# arm_schematic.net
KiCad netlist of a schematic drawn in EAGLE
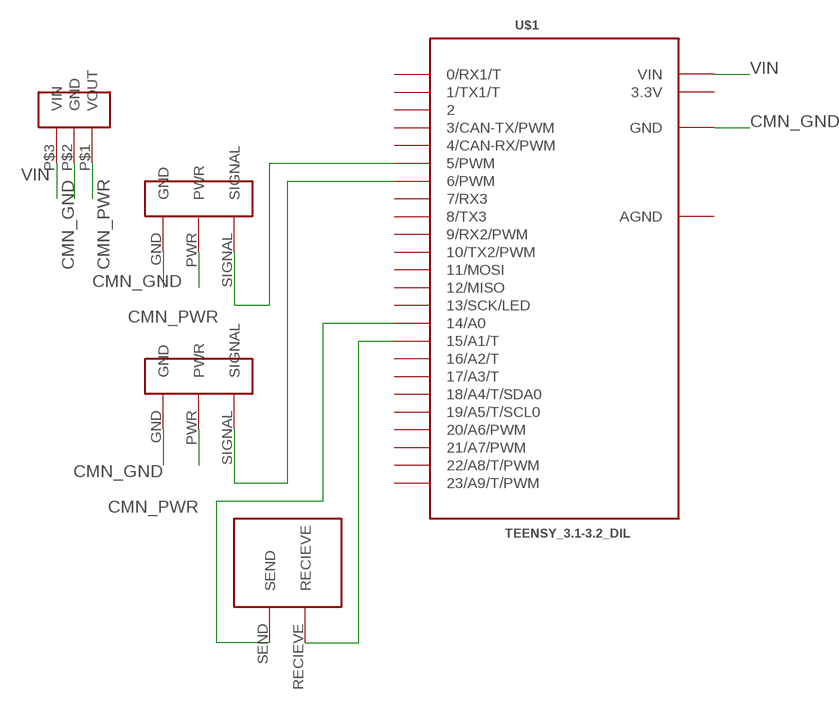
[diagram p0: schematic, sheet 1]

(export (version "E")
  (design (tool "Eeschema 10.0.6"))
  (components
    (comp (ref "U$1")
      (value "TEENSY_3.1-3.2_DIL")
      (footprint "eagle-import:TEENSY_3.0-3.2&LC_DIL")
      (libsource (lib "eagle-import") (part "TEENSY_3.1-3.2_DIL"))
    )
    (comp (ref "U$2")
      (value "VOLTAGE_REGULATOR")
      (footprint "eagle-import:VOLTAGE_REGULATOR")
      (libsource (lib "eagle-import") (part "VOLTAGE_REGULATOR"))
    )
    (comp (ref "U$3")
      (value "CUSTOM_BIT_COMM")
      (footprint "eagle-import:CUSTOM_BIT_COMM")
      (libsource (lib "eagle-import") (part "CUSTOM_BIT_COMM"))
    )
    (comp (ref "U$6")
      (value "ARM_CONNECTION")
      (footprint "eagle-import:ARM_CONNECTION")
      (libsource (lib "eagle-import") (part "ARM_CONNECTION"))
    )
    (comp (ref "U$7")
      (value "ARM_CONNECTION")
      (footprint "eagle-import:ARM_CONNECTION")
      (libsource (lib "eagle-import") (part "ARM_CONNECTION"))
    )
  )
  (nets
    (net (code "1") (name "/3.3V") (class "Default")
      (node (ref "U$1") (pin "3.3V") (pinfunction "3.3V_3.3V") (pintype "power_in"))
    )
    (net (code "2") (name "/AGND") (class "Default")
      (node (ref "U$1") (pin "AGND") (pinfunction "AGND_AGND") (pintype "power_in"))
    )
    (net (code "3") (name "/CMN_GND") (class "Default")
      (node (ref "U$1") (pin "GND") (pinfunction "GND_GND") (pintype "power_in"))
      (node (ref "U$2") (pin "P$2") (pinfunction "GND_P$2") (pintype "bidirectional"))
      (node (ref "U$6") (pin "GND") (pinfunction "GND_GND") (pintype "bidirectional"))
      (node (ref "U$7") (pin "GND") (pinfunction "GND_GND") (pintype "bidirectional"))
    )
    (net (code "4") (name "/CMN_PWR") (class "Default")
      (node (ref "U$2") (pin "P$1") (pinfunction "VOUT_P$1") (pintype "bidirectional"))
      (node (ref "U$6") (pin "PWR") (pinfunction "PWR_PWR") (pintype "bidirectional"))
      (node (ref "U$7") (pin "PWR") (pinfunction "PWR_PWR") (pintype "bidirectional"))
    )
    (net (code "5") (name "/VIN") (class "Default")
      (node (ref "U$1") (pin "VIN") (pinfunction "VIN_VIN") (pintype "power_in"))
      (node (ref "U$2") (pin "P$3") (pinfunction "VIN_P$3") (pintype "bidirectional"))
    )
    (net (code "6") (name "Net-(U$1-5{slash}PWM)") (class "Default")
      (node (ref "U$1") (pin "5") (pinfunction "5/PWM_5") (pintype "bidirectional"))
      (node (ref "U$6") (pin "SIGNAL") (pinfunction "SIGNAL_SIGNAL") (pintype "bidirectional"))
    )
    (net (code "7") (name "Net-(U$1-6{slash}PWM)") (class "Default")
      (node (ref "U$1") (pin "6") (pinfunction "6/PWM_6") (pintype "bidirectional"))
      (node (ref "U$7") (pin "SIGNAL") (pinfunction "SIGNAL_SIGNAL") (pintype "bidirectional"))
    )
    (net (code "8") (name "Net-(U$1-15{slash}A1{slash}T)") (class "Default")
      (node (ref "U$1") (pin "15/A1") (pinfunction "15/A1/T_15/A1") (pintype "bidirectional"))
      (node (ref "U$3") (pin "RECIEVE") (pinfunction "RECIEVE_RECIEVE") (pintype "bidirectional"))
    )
    (net (code "9") (name "Net-(U$1-Pad14{slash}A0)") (class "Default")
      (node (ref "U$1") (pin "14/A0") (pinfunction "14/A0_14/A0") (pintype "bidirectional"))
      (node (ref "U$3") (pin "SEND") (pinfunction "SEND_SEND") (pintype "bidirectional"))
    )
    (net (code "10") (name "unconnected-(U$1-0{slash}RX1{slash}T-Pad0)") (class "Default")
      (node (ref "U$1") (pin "0") (pinfunction "0/RX1/T_0") (pintype "bidirectional"))
    )
    (net (code "11") (name "unconnected-(U$1-1{slash}TX1{slash}T-Pad1)") (class "Default")
      (node (ref "U$1") (pin "1") (pinfunction "1/TX1/T_1") (pintype "bidirectional"))
    )
    (net (code "12") (name "unconnected-(U$1-3{slash}CAN-TX{slash}PWM-Pad3)") (class "Default")
      (node (ref "U$1") (pin "3") (pinfunction "3/CAN-TX/PWM_3") (pintype "bidirectional"))
    )
    (net (code "13") (name "unconnected-(U$1-4{slash}CAN-RX{slash}PWM-Pad4)") (class "Default")
      (node (ref "U$1") (pin "4") (pinfunction "4/CAN-RX/PWM_4") (pintype "bidirectional"))
    )
    (net (code "14") (name "unconnected-(U$1-7{slash}RX3-Pad7)") (class "Default")
      (node (ref "U$1") (pin "7") (pinfunction "7/RX3_7") (pintype "bidirectional"))
    )
    (net (code "15") (name "unconnected-(U$1-8{slash}TX3-Pad8)") (class "Default")
      (node (ref "U$1") (pin "8") (pinfunction "8/TX3_8") (pintype "bidirectional"))
    )
    (net (code "16") (name "unconnected-(U$1-9{slash}RX2{slash}PWM-Pad9)") (class "Default")
      (node (ref "U$1") (pin "9") (pinfunction "9/RX2/PWM_9") (pintype "bidirectional"))
    )
    (net (code "17") (name "unconnected-(U$1-10{slash}TX2{slash}PWM-Pad10)") (class "Default")
      (node (ref "U$1") (pin "10") (pinfunction "10/TX2/PWM_10") (pintype "bidirectional"))
    )
    (net (code "18") (name "unconnected-(U$1-11{slash}MOSI-Pad11)") (class "Default")
      (node (ref "U$1") (pin "11") (pinfunction "11/MOSI_11") (pintype "bidirectional"))
    )
    (net (code "19") (name "unconnected-(U$1-12{slash}MISO-Pad12)") (class "Default")
      (node (ref "U$1") (pin "12") (pinfunction "12/MISO_12") (pintype "bidirectional"))
    )
    (net (code "20") (name "unconnected-(U$1-13{slash}SCK{slash}LED-Pad13)") (class "Default")
      (node (ref "U$1") (pin "13") (pinfunction "13/SCK/LED_13") (pintype "bidirectional"))
    )
    (net (code "21") (name "unconnected-(U$1-16{slash}A2{slash}T-Pad16{slash}A2)") (class "Default")
      (node (ref "U$1") (pin "16/A2") (pinfunction "16/A2/T_16/A2") (pintype "bidirectional"))
    )
    (net (code "22") (name "unconnected-(U$1-17{slash}A3{slash}T-Pad17{slash}A3)") (class "Default")
      (node (ref "U$1") (pin "17/A3") (pinfunction "17/A3/T_17/A3") (pintype "bidirectional"))
    )
    (net (code "23") (name "unconnected-(U$1-18{slash}A4{slash}T{slash}SDA0-Pad18{slash}A4)") (class "Default")
      (node (ref "U$1") (pin "18/A4") (pinfunction "18/A4/T/SDA0_18/A4") (pintype "bidirectional"))
    )
    (net (code "24") (name "unconnected-(U$1-19{slash}A5{slash}T{slash}SCL0-Pad19{slash}A5)") (class "Default")
      (node (ref "U$1") (pin "19/A5") (pinfunction "19/A5/T/SCL0_19/A5") (pintype "bidirectional"))
    )
    (net (code "25") (name "unconnected-(U$1-20{slash}A6{slash}PWM-Pad20{slash}A6)") (class "Default")
      (node (ref "U$1") (pin "20/A6") (pinfunction "20/A6/PWM_20/A6") (pintype "bidirectional"))
    )
    (net (code "26") (name "unconnected-(U$1-21{slash}A7{slash}PWM-Pad21{slash}A7)") (class "Default")
      (node (ref "U$1") (pin "21/A7") (pinfunction "21/A7/PWM_21/A7") (pintype "bidirectional"))
    )
    (net (code "27") (name "unconnected-(U$1-22{slash}A8{slash}T{slash}PWM-Pad22{slash}A8)") (class "Default")
      (node (ref "U$1") (pin "22/A8") (pinfunction "22/A8/T/PWM_22/A8") (pintype "bidirectional"))
    )
    (net (code "28") (name "unconnected-(U$1-23{slash}A9{slash}T{slash}PWM-Pad23{slash}A9)") (class "Default")
      (node (ref "U$1") (pin "23/A9") (pinfunction "23/A9/T/PWM_23/A9") (pintype "bidirectional"))
    )
    (net (code "29") (name "unconnected-(U$1-Pad2)") (class "Default")
      (node (ref "U$1") (pin "2") (pinfunction "2_2") (pintype "bidirectional"))
    )
  )
)
